# CAN.net
KiCad netlist of a schematic drawn in Altium Designer
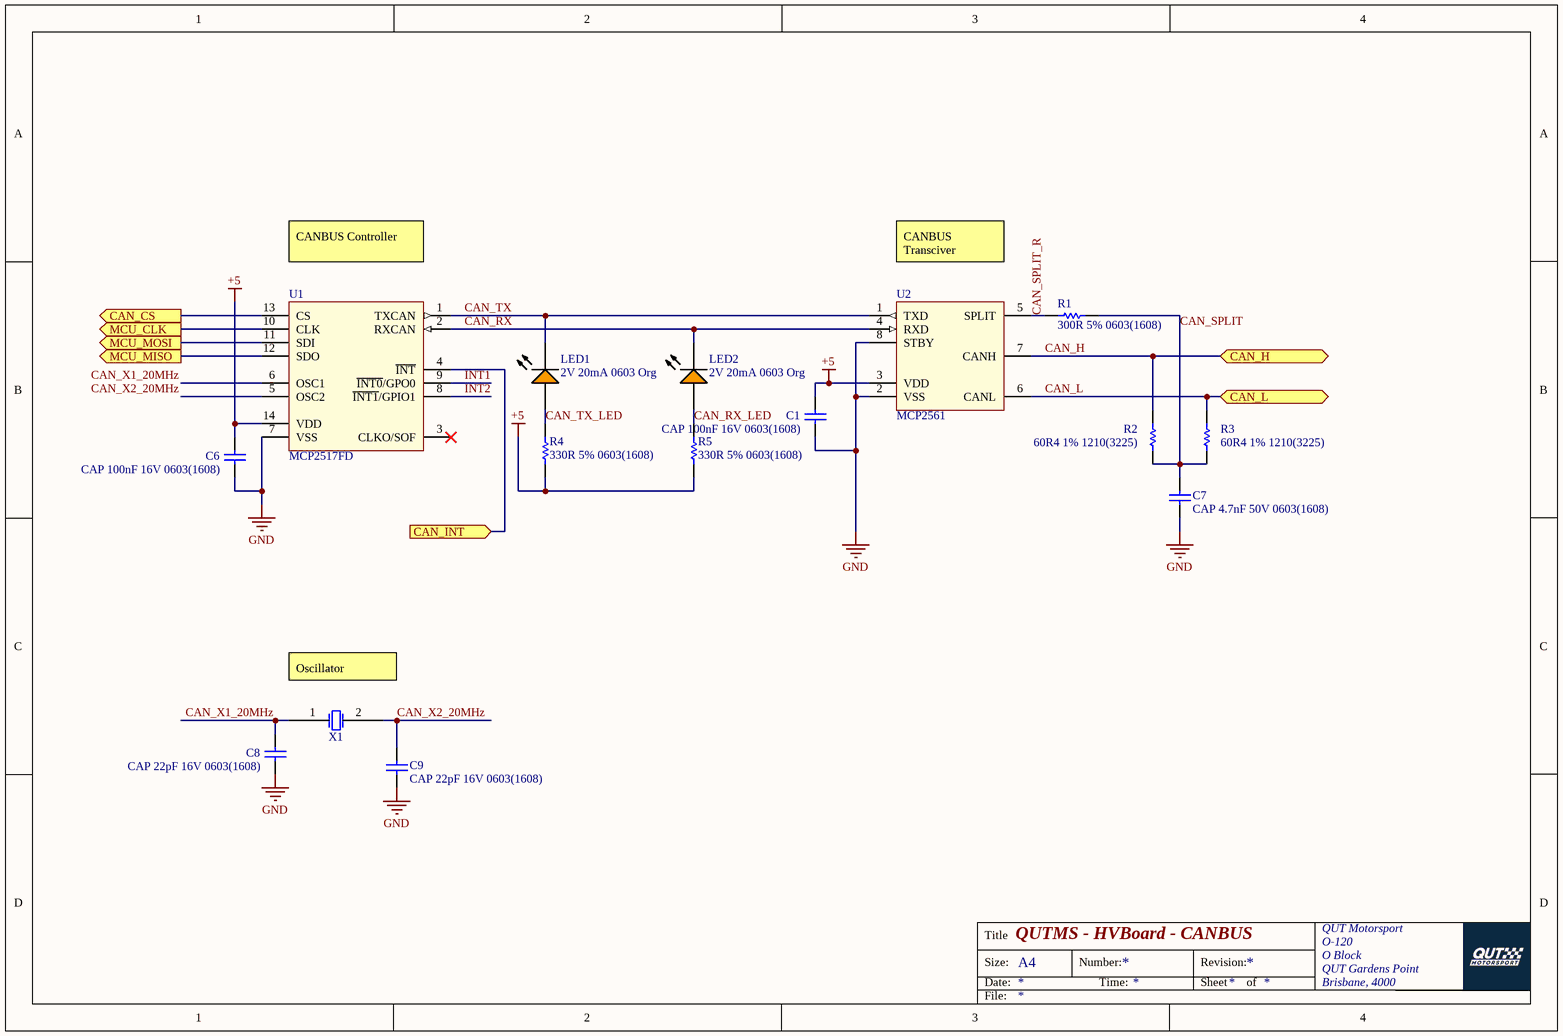
[diagram p0: CAN.SchDoc]

(export (version "E")
  (design (tool "Eeschema 10.0.6"))
  (components
    (comp (ref "C1")
      (value "CAP 100nF 16V 0603(1608)")
      (footprint "CAPC0603(1608)100_N")
      (description "CAP 100nF 16V ±10% 0603 (1608 Metric) Thickness 1mm SMD")
      (fields (field (name "TOLERANCE") "Â±10%"))
      (libsource (lib "Altium Content Vault") (part "CAP"))
    )
    (comp (ref "C6")
      (value "CAP 100nF 16V 0603(1608)")
      (footprint "CAPC0603(1608)100_N")
      (description "CAP 100nF 16V ±10% 0603 (1608 Metric) Thickness 1mm SMD")
      (fields (field (name "TOLERANCE") "Â±10%"))
      (libsource (lib "Altium Content Vault") (part "CAP"))
    )
    (comp (ref "C7")
      (value "CAP 4.7nF 50V 0603(1608)")
      (footprint "CAPC0603(1608)100_M")
      (description "CAP 4.7nF 50V ±5% 0603 (1608 Metric) Thickness 1mm SMD")
      (fields (field (name "TOLERANCE") "Â±5%"))
      (libsource (lib "Altium Content Vault") (part "CAP"))
    )
    (comp (ref "C8")
      (value "CAP 22pF 16V 0603(1608)")
      (footprint "CAPC0603(1608)100_N")
      (description "CAP 22pF 16V ±5% 0603 (1608 Metric) Thickness 1mm SMD")
      (fields (field (name "TOLERANCE") "Â±5%"))
      (libsource (lib "Altium Content Vault") (part "CAP"))
    )
    (comp (ref "C9")
      (value "CAP 22pF 16V 0603(1608)")
      (footprint "CAPC0603(1608)100_N")
      (description "CAP 22pF 16V ±5% 0603 (1608 Metric) Thickness 1mm SMD")
      (fields (field (name "TOLERANCE") "Â±5%"))
      (libsource (lib "Altium Content Vault") (part "CAP"))
    )
    (comp (ref "LED1")
      (value "2V 20mA 0603 Org")
      (footprint "KING-LED0603-25-ORANGE_V")
      (description "LED, SMT, 0603(1608), 0.25mm Tthickness, Super Bright Orange")
      (fields (field (name "PARTNUMBER") "APG1608SEKC/T"))
      (libsource (lib "Altium Content Vault") (part "KING-LED_ORANGE_A1K2-2"))
    )
    (comp (ref "LED2")
      (value "2V 20mA 0603 Org")
      (footprint "KING-LED0603-25-ORANGE_V")
      (description "LED, SMT, 0603(1608), 0.25mm Tthickness, Super Bright Orange")
      (fields (field (name "PARTNUMBER") "APG1608SEKC/T"))
      (libsource (lib "Altium Content Vault") (part "KING-LED_ORANGE_A1K2-2"))
    )
    (comp (ref "R1")
      (value "300R 5% 0603(1608)")
      (footprint "RESC0603(1608)_N")
      (description "300R 0.1W 5% 0603 (1608 Metric)  SMD")
      (fields (field (name "TOLERANCE") "5 %") (field (name "POWER") "0.1 W"))
      (libsource (lib "Altium Content Vault") (part "RES"))
    )
    (comp (ref "R2")
      (value "60R4 1% 1210(3225)")
      (footprint "RESC1210(3225)_L")
      (description "60R4 0.5W 1% 1210 (3225 Metric)  SMD")
      (fields (field (name "TOLERANCE") "1 %") (field (name "POWER") "0.5 W"))
      (libsource (lib "Altium Content Vault") (part "RES"))
    )
    (comp (ref "R3")
      (value "60R4 1% 1210(3225)")
      (footprint "RESC1210(3225)_L")
      (description "60R4 0.5W 1% 1210 (3225 Metric)  SMD")
      (fields (field (name "TOLERANCE") "1 %") (field (name "POWER") "0.5 W"))
      (libsource (lib "Altium Content Vault") (part "RES"))
    )
    (comp (ref "R4")
      (value "330R 5% 0603(1608)")
      (footprint "RESC0603(1608)_L")
      (description "330R 0.1W 5% 0603 (1608 Metric)  SMD")
      (fields (field (name "TOLERANCE") "5 %") (field (name "POWER") "0.1 W"))
      (libsource (lib "Altium Content Vault") (part "RES"))
    )
    (comp (ref "R5")
      (value "330R 5% 0603(1608)")
      (footprint "RESC0603(1608)_L")
      (description "330R 0.1W 5% 0603 (1608 Metric)  SMD")
      (fields (field (name "TOLERANCE") "5 %") (field (name "POWER") "0.1 W"))
      (libsource (lib "Altium Content Vault") (part "RES"))
    )
    (comp (ref "U1")
      (value "MCP2517FD")
      (footprint "MCP2517FD SOIC")
      (libsource (lib "QUTMS_CANLibrary") (part "MCP2517FD"))
    )
    (comp (ref "U2")
      (value "MCP2561")
      (footprint "MCP2561 SOIC")
      (libsource (lib "QUTMS_CANLibrary") (part "MCP2561"))
    )
    (comp (ref "X1")
      (value "Crystal 20MHz")
      (footprint "Crystal 20MHz")
      (libsource (lib "QUTMS_CrystalLibrary") (part "Crystal 20MHz"))
    )
  )
  (nets
    (net (code "1") (name "+5") (class "Default")
      (node (ref "C1") (pin "2") (pinfunction "2_2") (pintype "passive"))
      (node (ref "C6") (pin "2") (pinfunction "2_2") (pintype "passive"))
      (node (ref "R4") (pin "2") (pinfunction "2_2") (pintype "passive"))
      (node (ref "R5") (pin "2") (pinfunction "2_2") (pintype "passive"))
      (node (ref "U1") (pin "14") (pinfunction "VDD_14") (pintype "passive"))
      (node (ref "U2") (pin "3") (pinfunction "VDD_3") (pintype "passive"))
    )
    (net (code "2") (name "/CAN_CS") (class "Default")
      (node (ref "U1") (pin "13") (pinfunction "CS_13") (pintype "passive"))
    )
    (net (code "3") (name "/CAN_H") (class "Default")
      (node (ref "R2") (pin "2") (pinfunction "2_2") (pintype "passive"))
      (node (ref "U2") (pin "7") (pinfunction "CANH_7") (pintype "passive"))
    )
    (net (code "4") (name "/CAN_INT") (class "Default")
      (node (ref "U1") (pin "4") (pinfunction "~{INT}_4") (pintype "passive"))
    )
    (net (code "5") (name "/CAN_L") (class "Default")
      (node (ref "R3") (pin "2") (pinfunction "2_2") (pintype "passive"))
      (node (ref "U2") (pin "6") (pinfunction "CANL_6") (pintype "passive"))
    )
    (net (code "6") (name "/CAN_RX") (class "Default")
      (node (ref "LED2") (pin "2") (pinfunction "K_2") (pintype "passive"))
      (node (ref "U1") (pin "2") (pinfunction "RXCAN_2") (pintype "input"))
      (node (ref "U2") (pin "4") (pinfunction "RXD_4") (pintype "input"))
    )
    (net (code "7") (name "/CAN_RX_LED") (class "Default")
      (node (ref "LED2") (pin "1") (pinfunction "A_1") (pintype "passive"))
      (node (ref "R5") (pin "1") (pinfunction "1_1") (pintype "passive"))
    )
    (net (code "8") (name "/CAN_SPLIT") (class "Default")
      (node (ref "C7") (pin "2") (pinfunction "2_2") (pintype "passive"))
      (node (ref "R1") (pin "2") (pinfunction "2_2") (pintype "passive"))
      (node (ref "R2") (pin "1") (pinfunction "1_1") (pintype "passive"))
      (node (ref "R3") (pin "1") (pinfunction "1_1") (pintype "passive"))
    )
    (net (code "9") (name "/CAN_SPLIT_R") (class "Default")
      (node (ref "R1") (pin "1") (pinfunction "1_1") (pintype "passive"))
      (node (ref "U2") (pin "5") (pinfunction "SPLIT_5") (pintype "passive"))
    )
    (net (code "10") (name "/CAN_TX") (class "Default")
      (node (ref "LED1") (pin "2") (pinfunction "K_2") (pintype "passive"))
      (node (ref "U1") (pin "1") (pinfunction "TXCAN_1") (pintype "output"))
      (node (ref "U2") (pin "1") (pinfunction "TXD_1") (pintype "output"))
    )
    (net (code "11") (name "/CAN_TX_LED") (class "Default")
      (node (ref "LED1") (pin "1") (pinfunction "A_1") (pintype "passive"))
      (node (ref "R4") (pin "1") (pinfunction "1_1") (pintype "passive"))
    )
    (net (code "12") (name "/CAN_X1_20MHz") (class "Default")
      (node (ref "C8") (pin "2") (pinfunction "2_2") (pintype "passive"))
      (node (ref "U1") (pin "6") (pinfunction "OSC1_6") (pintype "passive"))
      (node (ref "X1") (pin "1") (pintype "passive"))
    )
    (net (code "13") (name "/CAN_X2_20MHz") (class "Default")
      (node (ref "C9") (pin "1") (pinfunction "1_1") (pintype "passive"))
      (node (ref "U1") (pin "5") (pinfunction "OSC2_5") (pintype "passive"))
      (node (ref "X1") (pin "2") (pintype "passive"))
    )
    (net (code "14") (name "/INT1") (class "Default")
      (node (ref "U1") (pin "9") (pinfunction "~{INT0}/GPO0_9") (pintype "passive"))
    )
    (net (code "15") (name "/INT2") (class "Default")
      (node (ref "U1") (pin "8") (pinfunction "~{INT1}/GPIO1_8") (pintype "passive"))
    )
    (net (code "16") (name "/MCU_CLK") (class "Default")
      (node (ref "U1") (pin "10") (pinfunction "CLK_10") (pintype "passive"))
    )
    (net (code "17") (name "/MCU_MISO") (class "Default")
      (node (ref "U1") (pin "12") (pinfunction "SDO_12") (pintype "passive"))
    )
    (net (code "18") (name "/MCU_MOSI") (class "Default")
      (node (ref "U1") (pin "11") (pinfunction "SDI_11") (pintype "passive"))
    )
    (net (code "19") (name "GND") (class "Default")
      (node (ref "C1") (pin "1") (pinfunction "1_1") (pintype "passive"))
      (node (ref "C6") (pin "1") (pinfunction "1_1") (pintype "passive"))
      (node (ref "C7") (pin "1") (pinfunction "1_1") (pintype "passive"))
      (node (ref "C8") (pin "1") (pinfunction "1_1") (pintype "passive"))
      (node (ref "C9") (pin "2") (pinfunction "2_2") (pintype "passive"))
      (node (ref "U1") (pin "7") (pinfunction "VSS_7") (pintype "passive"))
      (node (ref "U2") (pin "2") (pinfunction "VSS_2") (pintype "passive"))
      (node (ref "U2") (pin "8") (pinfunction "STBY_8") (pintype "passive"))
    )
    (net (code "20") (name "unconnected-(U1-CLKO{slash}SOF-Pad3)") (class "Default")
      (node (ref "U1") (pin "3") (pinfunction "CLKO/SOF_3") (pintype "passive+no_connect"))
    )
  )
)
